# i2c0.net
KiCad netlist of a schematic drawn in Altium Designer
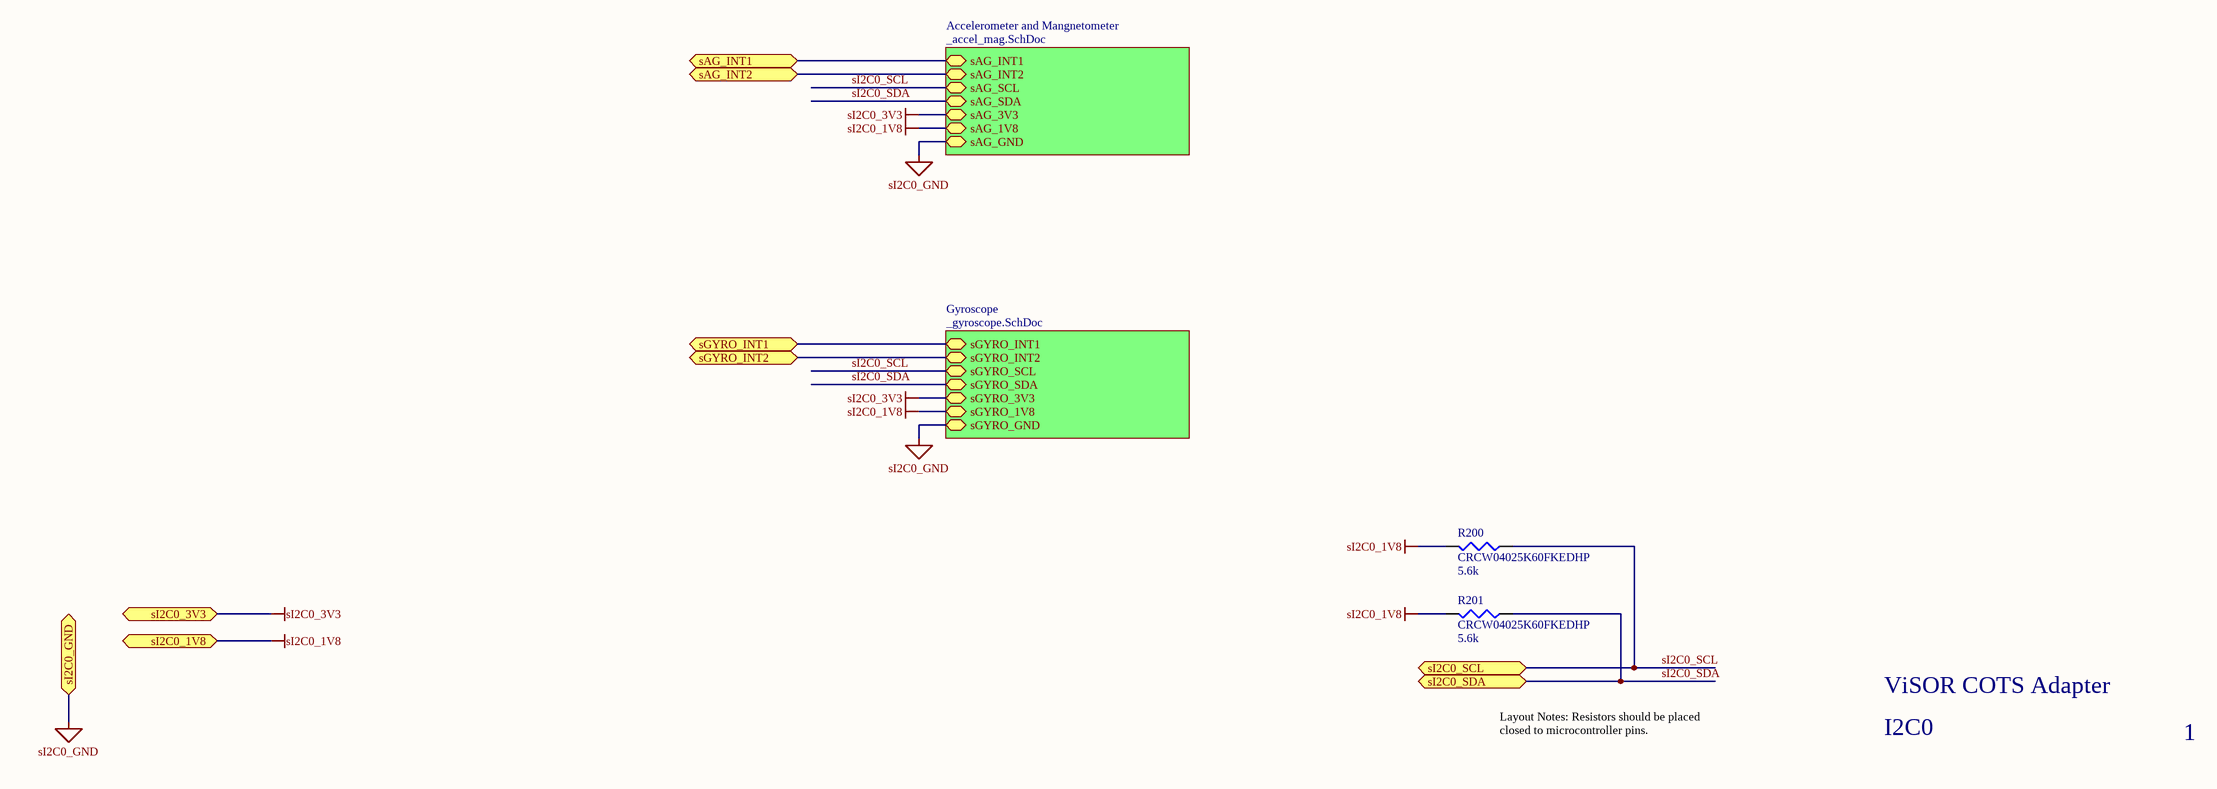
[diagram p0: _i2c0.SchDoc]

(export (version "E")
  (design (tool "Eeschema 10.0.6"))
  (components
    (comp (ref "R200")
      (value "CRCW04025K60FKEDHP")
      (footprint "0402")
      (description "0.125W, -55-155C, 1005, 50V, ±1%")
      (fields (field (name "ALTIUM_VALUE") "5.6k"))
      (libsource (lib "standard_resistors") (part "CRCW0402xxxxFKED"))
    )
    (comp (ref "R201")
      (value "CRCW04025K60FKEDHP")
      (footprint "0402")
      (description "0.125W, -55-155C, 1005, 50V, ±1%")
      (fields (field (name "ALTIUM_VALUE") "5.6k"))
      (libsource (lib "standard_resistors") (part "CRCW0402xxxxFKED"))
    )
  )
  (nets
    (net (code "5") (name "/sI2C0_SCL") (class "Default")
      (node (ref "R200") (pin "1") (pinfunction "1_1") (pintype "passive"))
    )
    (net (code "6") (name "/sI2C0_SDA") (class "Default")
      (node (ref "R201") (pin "1") (pinfunction "1_1") (pintype "passive"))
    )
    (net (code "7") (name "sI2C0_1V8") (class "Default")
      (node (ref "R200") (pin "2") (pinfunction "2_2") (pintype "passive"))
      (node (ref "R201") (pin "2") (pinfunction "2_2") (pintype "passive"))
    )
  )
)
